# RobOnPi.net
KiCad netlist of a schematic drawn in EAGLE
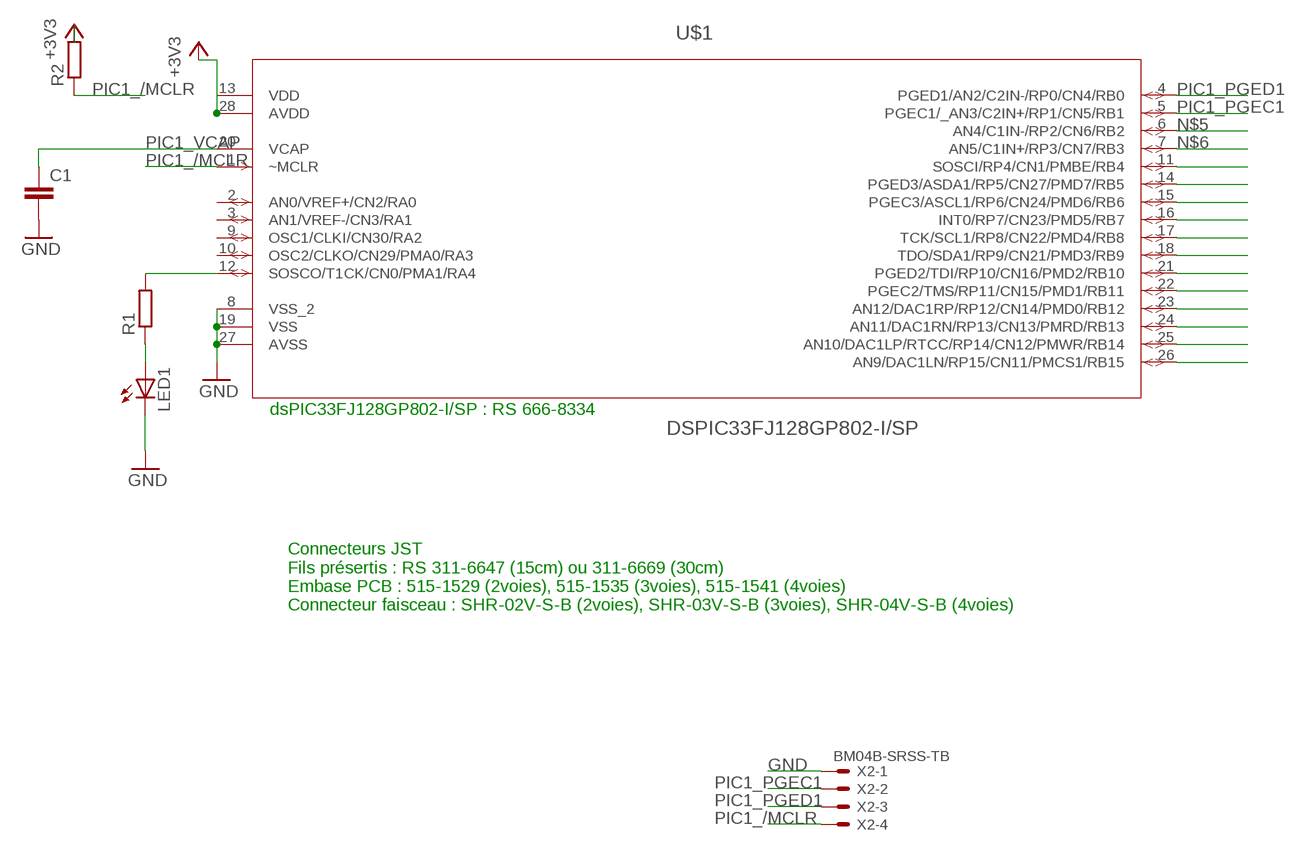
[diagram p0: schematic, sheet 1]

(export (version "E")
  (design (tool "Eeschema 10.0.6"))
  (components
    (comp (ref "C1")
      (value "C-EUC1206")
      (footprint "eagle-import:C1206")
      (libsource (lib "eagle-import") (part "C-EUC1206"))
    )
    (comp (ref "LED1")
      (value "LEDSML1206")
      (footprint "eagle-import:SML1206")
      (libsource (lib "eagle-import") (part "LEDSML1206"))
    )
    (comp (ref "R1")
      (value "R-EU_M1206")
      (footprint "eagle-import:M1206")
      (libsource (lib "eagle-import") (part "R-EU_M1206"))
    )
    (comp (ref "R2")
      (value "R-EU_M1206")
      (footprint "eagle-import:M1206")
      (libsource (lib "eagle-import") (part "R-EU_M1206"))
    )
    (comp (ref "U$1")
      (value "DSPIC33FJ128GP802-I/SP")
      (footprint "eagle-import:DIP254P762X508-28")
      (libsource (lib "eagle-import") (part "DSPIC33FJ128GP802-I/SP"))
    )
    (comp (ref "X2")
      (value "BM04B-SRSS-TB")
      (footprint "eagle-import:BM04B-SRSS-TB")
      (libsource (lib "eagle-import") (part "?M04B-SRSS-TBB"))
    )
  )
  (nets
    (net (code "1") (name "+3V3") (class "Default")
      (node (ref "R2") (pin "2") (pinfunction "2_2") (pintype "passive"))
      (node (ref "U$1") (pin "13") (pinfunction "VDD_13") (pintype "power_in"))
      (node (ref "U$1") (pin "28") (pinfunction "AVDD_28") (pintype "power_in"))
    )
    (net (code "2") (name "GND") (class "Default")
      (node (ref "C1") (pin "2") (pinfunction "2_2") (pintype "passive"))
      (node (ref "LED1") (pin "C") (pinfunction "C_C") (pintype "passive"))
      (node (ref "U$1") (pin "19") (pinfunction "VSS_19") (pintype "power_in"))
      (node (ref "U$1") (pin "27") (pinfunction "AVSS_27") (pintype "power_in"))
      (node (ref "U$1") (pin "8") (pinfunction "VSS_2_8") (pintype "power_in"))
      (node (ref "X2") (pin "1") (pinfunction "S_1") (pintype "passive"))
    )
    (net (code "3") (name "N$5") (class "Default")
      (node (ref "U$1") (pin "6") (pinfunction "AN4/C1IN-/RP2/CN6/RB2_6") (pintype "bidirectional"))
    )
    (net (code "4") (name "N$6") (class "Default")
      (node (ref "U$1") (pin "7") (pinfunction "AN5/C1IN+/RP3/CN7/RB3_7") (pintype "bidirectional"))
    )
    (net (code "5") (name "Net-(LED1-PadA)") (class "Default")
      (node (ref "LED1") (pin "A") (pinfunction "A_A") (pintype "passive"))
      (node (ref "R1") (pin "1") (pinfunction "1_1") (pintype "passive"))
    )
    (net (code "6") (name "Net-(U$1-SOSCO{slash}T1CK{slash}CN0{slash}PMA1{slash}RA4)") (class "Default")
      (node (ref "R1") (pin "2") (pinfunction "2_2") (pintype "passive"))
      (node (ref "U$1") (pin "12") (pinfunction "SOSCO/T1CK/CN0/PMA1/RA4_12") (pintype "bidirectional"))
    )
    (net (code "7") (name "PIC1_PGEC1") (class "Default")
      (node (ref "U$1") (pin "5") (pinfunction "PGEC1/_AN3/C2IN+/RP1/CN5/RB1_5") (pintype "bidirectional"))
      (node (ref "X2") (pin "2") (pinfunction "S_2") (pintype "passive"))
    )
    (net (code "8") (name "PIC1_PGED1") (class "Default")
      (node (ref "U$1") (pin "4") (pinfunction "PGED1/AN2/C2IN-/RP0/CN4/RB0_4") (pintype "bidirectional"))
      (node (ref "X2") (pin "3") (pinfunction "S_3") (pintype "passive"))
    )
    (net (code "9") (name "PIC1_VCAP") (class "Default")
      (node (ref "C1") (pin "1") (pinfunction "1_1") (pintype "passive"))
      (node (ref "U$1") (pin "20") (pinfunction "VCAP_20") (pintype "power_in"))
    )
    (net (code "10") (name "PIC1_{slash}MCLR") (class "Default")
      (node (ref "R2") (pin "1") (pinfunction "1_1") (pintype "passive"))
      (node (ref "U$1") (pin "1") (pinfunction "~{MCLR}_1") (pintype "input"))
      (node (ref "X2") (pin "4") (pinfunction "S_4") (pintype "passive"))
    )
    (net (code "11") (name "unconnected-(U$1-AN0{slash}VREF+{slash}CN2{slash}RA0-Pad2)") (class "Default")
      (node (ref "U$1") (pin "2") (pinfunction "AN0/VREF+/CN2/RA0_2") (pintype "bidirectional"))
    )
    (net (code "12") (name "unconnected-(U$1-AN1{slash}VREF-{slash}CN3{slash}RA1-Pad3)") (class "Default")
      (node (ref "U$1") (pin "3") (pinfunction "AN1/VREF-/CN3/RA1_3") (pintype "bidirectional"))
    )
    (net (code "13") (name "unconnected-(U$1-AN9{slash}DAC1LN{slash}RP15{slash}CN11{slash}PMCS1{slash}RB15-Pad26)") (class "Default")
      (node (ref "U$1") (pin "26") (pinfunction "AN9/DAC1LN/RP15/CN11/PMCS1/RB15_26") (pintype "bidirectional"))
    )
    (net (code "14") (name "unconnected-(U$1-AN10{slash}DAC1LP{slash}RTCC{slash}RP14{slash}CN12{slash}PMWR{slash}RB14-Pad25)") (class "Default")
      (node (ref "U$1") (pin "25") (pinfunction "AN10/DAC1LP/RTCC/RP14/CN12/PMWR/RB14_25") (pintype "bidirectional"))
    )
    (net (code "15") (name "unconnected-(U$1-AN11{slash}DAC1RN{slash}RP13{slash}CN13{slash}PMRD{slash}RB13-Pad24)") (class "Default")
      (node (ref "U$1") (pin "24") (pinfunction "AN11/DAC1RN/RP13/CN13/PMRD/RB13_24") (pintype "bidirectional"))
    )
    (net (code "16") (name "unconnected-(U$1-AN12{slash}DAC1RP{slash}RP12{slash}CN14{slash}PMD0{slash}RB12-Pad23)") (class "Default")
      (node (ref "U$1") (pin "23") (pinfunction "AN12/DAC1RP/RP12/CN14/PMD0/RB12_23") (pintype "bidirectional"))
    )
    (net (code "17") (name "unconnected-(U$1-INT0{slash}RP7{slash}CN23{slash}PMD5{slash}RB7-Pad16)") (class "Default")
      (node (ref "U$1") (pin "16") (pinfunction "INT0/RP7/CN23/PMD5/RB7_16") (pintype "bidirectional"))
    )
    (net (code "18") (name "unconnected-(U$1-OSC1{slash}CLKI{slash}CN30{slash}RA2-Pad9)") (class "Default")
      (node (ref "U$1") (pin "9") (pinfunction "OSC1/CLKI/CN30/RA2_9") (pintype "bidirectional"))
    )
    (net (code "19") (name "unconnected-(U$1-OSC2{slash}CLKO{slash}CN29{slash}PMA0{slash}RA3-Pad10)") (class "Default")
      (node (ref "U$1") (pin "10") (pinfunction "OSC2/CLKO/CN29/PMA0/RA3_10") (pintype "bidirectional"))
    )
    (net (code "20") (name "unconnected-(U$1-PGEC2{slash}TMS{slash}RP11{slash}CN15{slash}PMD1{slash}RB11-Pad22)") (class "Default")
      (node (ref "U$1") (pin "22") (pinfunction "PGEC2/TMS/RP11/CN15/PMD1/RB11_22") (pintype "bidirectional"))
    )
    (net (code "21") (name "unconnected-(U$1-PGEC3{slash}ASCL1{slash}RP6{slash}CN24{slash}PMD6{slash}RB6-Pad15)") (class "Default")
      (node (ref "U$1") (pin "15") (pinfunction "PGEC3/ASCL1/RP6/CN24/PMD6/RB6_15") (pintype "bidirectional"))
    )
    (net (code "22") (name "unconnected-(U$1-PGED2{slash}TDI{slash}RP10{slash}CN16{slash}PMD2{slash}RB10-Pad21)") (class "Default")
      (node (ref "U$1") (pin "21") (pinfunction "PGED2/TDI/RP10/CN16/PMD2/RB10_21") (pintype "bidirectional"))
    )
    (net (code "23") (name "unconnected-(U$1-PGED3{slash}ASDA1{slash}RP5{slash}CN27{slash}PMD7{slash}RB5-Pad14)") (class "Default")
      (node (ref "U$1") (pin "14") (pinfunction "PGED3/ASDA1/RP5/CN27/PMD7/RB5_14") (pintype "bidirectional"))
    )
    (net (code "24") (name "unconnected-(U$1-SOSCI{slash}RP4{slash}CN1{slash}PMBE{slash}RB4-Pad11)") (class "Default")
      (node (ref "U$1") (pin "11") (pinfunction "SOSCI/RP4/CN1/PMBE/RB4_11") (pintype "bidirectional"))
    )
    (net (code "25") (name "unconnected-(U$1-TCK{slash}SCL1{slash}RP8{slash}CN22{slash}PMD4{slash}RB8-Pad17)") (class "Default")
      (node (ref "U$1") (pin "17") (pinfunction "TCK/SCL1/RP8/CN22/PMD4/RB8_17") (pintype "bidirectional"))
    )
    (net (code "26") (name "unconnected-(U$1-TDO{slash}SDA1{slash}RP9{slash}CN21{slash}PMD3{slash}RB9-Pad18)") (class "Default")
      (node (ref "U$1") (pin "18") (pinfunction "TDO/SDA1/RP9/CN21/PMD3/RB9_18") (pintype "bidirectional"))
    )
  )
)
